# Keyboard_Buttons.net
KiCad netlist of a schematic drawn in Altium Designer
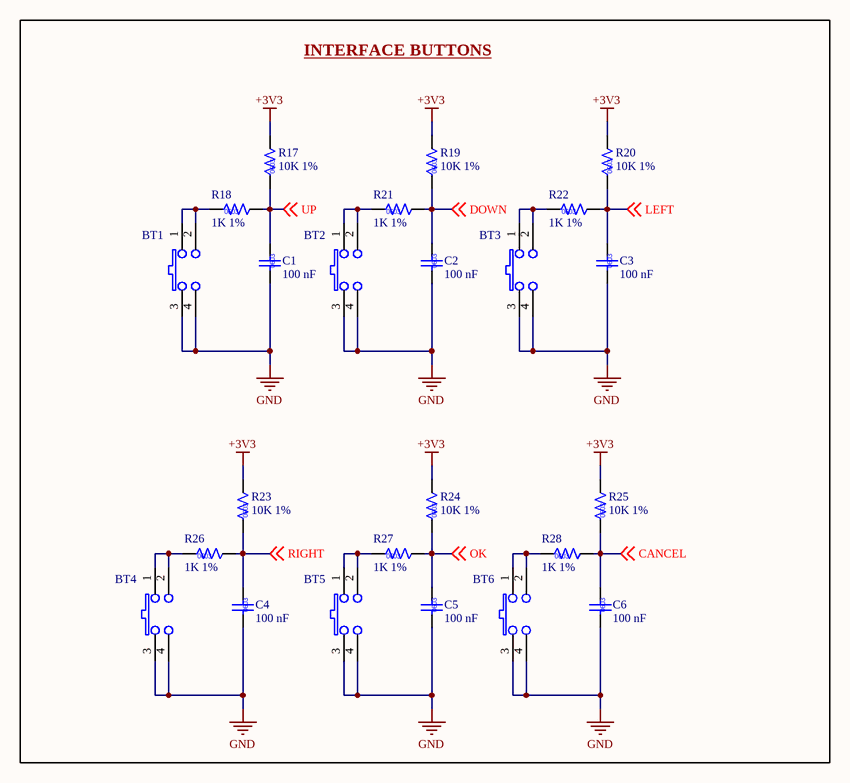
[diagram p0: Keyboard_Buttons.SchDoc]

(export (version "E")
  (design (tool "Eeschema 10.0.6"))
  (components
    (comp (ref "BT1")
      (value "TS14-1212-60-BK-260-SCR-D")
      (footprint "TS14121260BK260SCRD")
      (description "Interruptores táctiles 12 x 12 mm 6 mm 260 gf Short Crimped Black Through Hole SPST")
      (fields (field (name "MANUFACTURER") "Same Sky"))
      (libsource (lib "DDR5_Nucleo_Shield_Symbols") (part "TS14-1212-60-BK-260-SCR-D"))
    )
    (comp (ref "BT2")
      (value "TS14-1212-60-BK-260-SCR-D")
      (footprint "TS14121260BK260SCRD")
      (description "Interruptores táctiles 12 x 12 mm 6 mm 260 gf Short Crimped Black Through Hole SPST")
      (fields (field (name "MANUFACTURER") "Same Sky"))
      (libsource (lib "DDR5_Nucleo_Shield_Symbols") (part "TS14-1212-60-BK-260-SCR-D"))
    )
    (comp (ref "BT3")
      (value "TS14-1212-60-BK-260-SCR-D")
      (footprint "TS14121260BK260SCRD")
      (description "Interruptores táctiles 12 x 12 mm 6 mm 260 gf Short Crimped Black Through Hole SPST")
      (fields (field (name "MANUFACTURER") "Same Sky"))
      (libsource (lib "DDR5_Nucleo_Shield_Symbols") (part "TS14-1212-60-BK-260-SCR-D"))
    )
    (comp (ref "BT4")
      (value "TS14-1212-60-BK-260-SCR-D")
      (footprint "TS14121260BK260SCRD")
      (description "Interruptores táctiles 12 x 12 mm 6 mm 260 gf Short Crimped Black Through Hole SPST")
      (fields (field (name "MANUFACTURER") "Same Sky"))
      (libsource (lib "DDR5_Nucleo_Shield_Symbols") (part "TS14-1212-60-BK-260-SCR-D"))
    )
    (comp (ref "BT5")
      (value "TS14-1212-60-BK-260-SCR-D")
      (footprint "TS14121260BK260SCRD")
      (description "Interruptores táctiles 12 x 12 mm 6 mm 260 gf Short Crimped Black Through Hole SPST")
      (fields (field (name "MANUFACTURER") "Same Sky"))
      (libsource (lib "DDR5_Nucleo_Shield_Symbols") (part "TS14-1212-60-BK-260-SCR-D"))
    )
    (comp (ref "BT6")
      (value "TS14-1212-60-BK-260-SCR-D")
      (footprint "TS14121260BK260SCRD")
      (description "Interruptores táctiles 12 x 12 mm 6 mm 260 gf Short Crimped Black Through Hole SPST")
      (fields (field (name "MANUFACTURER") "Same Sky"))
      (libsource (lib "DDR5_Nucleo_Shield_Symbols") (part "TS14-1212-60-BK-260-SCR-D"))
    )
    (comp (ref "C1")
      (value "100 nF")
      (footprint "CC/NM 0603")
      (description "0.1 µF -20%, +80% 25V Ceramic Capacitor Y5V (F) 0603 (1608 Metric)")
      (fields
        (field (name "MANUFACTURER") "KYOCERA AVX")
        (field (name "MANUFACTURER PART NUMBER") "KGM15AV51E104ZM")
      )
      (libsource (lib "DDR5_Nucleo_Shield_Symbols") (part "KGM15AV51E104ZM"))
    )
    (comp (ref "C2")
      (value "100 nF")
      (footprint "CC/NM 0603")
      (description "0.1 µF -20%, +80% 25V Ceramic Capacitor Y5V (F) 0603 (1608 Metric)")
      (fields
        (field (name "MANUFACTURER") "KYOCERA AVX")
        (field (name "MANUFACTURER PART NUMBER") "KGM15AV51E104ZM")
      )
      (libsource (lib "DDR5_Nucleo_Shield_Symbols") (part "KGM15AV51E104ZM"))
    )
    (comp (ref "C3")
      (value "100 nF")
      (footprint "CC/NM 0603")
      (description "0.1 µF -20%, +80% 25V Ceramic Capacitor Y5V (F) 0603 (1608 Metric)")
      (fields
        (field (name "MANUFACTURER") "KYOCERA AVX")
        (field (name "MANUFACTURER PART NUMBER") "KGM15AV51E104ZM")
      )
      (libsource (lib "DDR5_Nucleo_Shield_Symbols") (part "KGM15AV51E104ZM"))
    )
    (comp (ref "C4")
      (value "100 nF")
      (footprint "CC/NM 0603")
      (description "0.1 µF -20%, +80% 25V Ceramic Capacitor Y5V (F) 0603 (1608 Metric)")
      (fields
        (field (name "MANUFACTURER") "KYOCERA AVX")
        (field (name "MANUFACTURER PART NUMBER") "KGM15AV51E104ZM")
      )
      (libsource (lib "DDR5_Nucleo_Shield_Symbols") (part "KGM15AV51E104ZM"))
    )
    (comp (ref "C5")
      (value "100 nF")
      (footprint "CC/NM 0603")
      (description "0.1 µF -20%, +80% 25V Ceramic Capacitor Y5V (F) 0603 (1608 Metric)")
      (fields
        (field (name "MANUFACTURER") "KYOCERA AVX")
        (field (name "MANUFACTURER PART NUMBER") "KGM15AV51E104ZM")
      )
      (libsource (lib "DDR5_Nucleo_Shield_Symbols") (part "KGM15AV51E104ZM"))
    )
    (comp (ref "C6")
      (value "100 nF")
      (footprint "CC/NM 0603")
      (description "0.1 µF -20%, +80% 25V Ceramic Capacitor Y5V (F) 0603 (1608 Metric)")
      (fields
        (field (name "MANUFACTURER") "KYOCERA AVX")
        (field (name "MANUFACTURER PART NUMBER") "KGM15AV51E104ZM")
      )
      (libsource (lib "DDR5_Nucleo_Shield_Symbols") (part "KGM15AV51E104ZM"))
    )
    (comp (ref "R17")
      (value "10K 1%")
      (footprint "CC/NM 0603")
      (fields
        (field (name "MANUFACTURER") "YAGEO")
        (field (name "MANUFACTURER PART NUMBER") "AC0603FR-0710KL")
      )
      (libsource (lib "DDR5_Nucleo_Shield_Symbols") (part "AC0603FR-0710KL"))
    )
    (comp (ref "R18")
      (value "1K 1%")
      (footprint "CC/NM 0603")
      (fields
        (field (name "MANUFACTURER") "YAGEO")
        (field (name "MANUFACTURER PART NUMBER") "RT0603BRD101KL")
      )
      (libsource (lib "DDR5_Nucleo_Shield_Symbols") (part "RT0603BRD101KL"))
    )
    (comp (ref "R19")
      (value "10K 1%")
      (footprint "CC/NM 0603")
      (fields
        (field (name "MANUFACTURER") "YAGEO")
        (field (name "MANUFACTURER PART NUMBER") "AC0603FR-0710KL")
      )
      (libsource (lib "DDR5_Nucleo_Shield_Symbols") (part "AC0603FR-0710KL"))
    )
    (comp (ref "R20")
      (value "10K 1%")
      (footprint "CC/NM 0603")
      (fields
        (field (name "MANUFACTURER") "YAGEO")
        (field (name "MANUFACTURER PART NUMBER") "AC0603FR-0710KL")
      )
      (libsource (lib "DDR5_Nucleo_Shield_Symbols") (part "AC0603FR-0710KL"))
    )
    (comp (ref "R21")
      (value "1K 1%")
      (footprint "CC/NM 0603")
      (fields
        (field (name "MANUFACTURER") "YAGEO")
        (field (name "MANUFACTURER PART NUMBER") "RT0603BRD101KL")
      )
      (libsource (lib "DDR5_Nucleo_Shield_Symbols") (part "RT0603BRD101KL"))
    )
    (comp (ref "R22")
      (value "1K 1%")
      (footprint "CC/NM 0603")
      (fields
        (field (name "MANUFACTURER") "YAGEO")
        (field (name "MANUFACTURER PART NUMBER") "RT0603BRD101KL")
      )
      (libsource (lib "DDR5_Nucleo_Shield_Symbols") (part "RT0603BRD101KL"))
    )
    (comp (ref "R23")
      (value "10K 1%")
      (footprint "CC/NM 0603")
      (fields
        (field (name "MANUFACTURER") "YAGEO")
        (field (name "MANUFACTURER PART NUMBER") "AC0603FR-0710KL")
      )
      (libsource (lib "DDR5_Nucleo_Shield_Symbols") (part "AC0603FR-0710KL"))
    )
    (comp (ref "R24")
      (value "10K 1%")
      (footprint "CC/NM 0603")
      (fields
        (field (name "MANUFACTURER") "YAGEO")
        (field (name "MANUFACTURER PART NUMBER") "AC0603FR-0710KL")
      )
      (libsource (lib "DDR5_Nucleo_Shield_Symbols") (part "AC0603FR-0710KL"))
    )
    (comp (ref "R25")
      (value "10K 1%")
      (footprint "CC/NM 0603")
      (fields
        (field (name "MANUFACTURER") "YAGEO")
        (field (name "MANUFACTURER PART NUMBER") "AC0603FR-0710KL")
      )
      (libsource (lib "DDR5_Nucleo_Shield_Symbols") (part "AC0603FR-0710KL"))
    )
    (comp (ref "R26")
      (value "1K 1%")
      (footprint "CC/NM 0603")
      (fields
        (field (name "MANUFACTURER") "YAGEO")
        (field (name "MANUFACTURER PART NUMBER") "RT0603BRD101KL")
      )
      (libsource (lib "DDR5_Nucleo_Shield_Symbols") (part "RT0603BRD101KL"))
    )
    (comp (ref "R27")
      (value "1K 1%")
      (footprint "CC/NM 0603")
      (fields
        (field (name "MANUFACTURER") "YAGEO")
        (field (name "MANUFACTURER PART NUMBER") "RT0603BRD101KL")
      )
      (libsource (lib "DDR5_Nucleo_Shield_Symbols") (part "RT0603BRD101KL"))
    )
    (comp (ref "R28")
      (value "1K 1%")
      (footprint "CC/NM 0603")
      (fields
        (field (name "MANUFACTURER") "YAGEO")
        (field (name "MANUFACTURER PART NUMBER") "RT0603BRD101KL")
      )
      (libsource (lib "DDR5_Nucleo_Shield_Symbols") (part "RT0603BRD101KL"))
    )
  )
  (nets
    (net (code "1") (name "+3V3") (class "Default")
      (node (ref "R17") (pin "2") (pinfunction "2_2") (pintype "passive"))
      (node (ref "R19") (pin "2") (pinfunction "2_2") (pintype "passive"))
      (node (ref "R20") (pin "2") (pinfunction "2_2") (pintype "passive"))
      (node (ref "R23") (pin "2") (pinfunction "2_2") (pintype "passive"))
      (node (ref "R24") (pin "2") (pinfunction "2_2") (pintype "passive"))
      (node (ref "R25") (pin "2") (pinfunction "2_2") (pintype "passive"))
    )
    (net (code "2") (name "CANCEL") (class "Default")
      (node (ref "C6") (pin "2") (pinfunction "2_2") (pintype "passive"))
      (node (ref "R25") (pin "1") (pinfunction "1_1") (pintype "passive"))
      (node (ref "R28") (pin "2") (pinfunction "2_2") (pintype "passive"))
    )
    (net (code "3") (name "DOWN") (class "Default")
      (node (ref "C2") (pin "2") (pinfunction "2_2") (pintype "passive"))
      (node (ref "R19") (pin "1") (pinfunction "1_1") (pintype "passive"))
      (node (ref "R21") (pin "2") (pinfunction "2_2") (pintype "passive"))
    )
    (net (code "4") (name "GND") (class "Default")
      (node (ref "BT1") (pin "3") (pinfunction "3_3") (pintype "passive"))
      (node (ref "BT1") (pin "4") (pinfunction "4_4") (pintype "passive"))
      (node (ref "BT2") (pin "3") (pinfunction "3_3") (pintype "passive"))
      (node (ref "BT2") (pin "4") (pinfunction "4_4") (pintype "passive"))
      (node (ref "BT3") (pin "3") (pinfunction "3_3") (pintype "passive"))
      (node (ref "BT3") (pin "4") (pinfunction "4_4") (pintype "passive"))
      (node (ref "BT4") (pin "3") (pinfunction "3_3") (pintype "passive"))
      (node (ref "BT4") (pin "4") (pinfunction "4_4") (pintype "passive"))
      (node (ref "BT5") (pin "3") (pinfunction "3_3") (pintype "passive"))
      (node (ref "BT5") (pin "4") (pinfunction "4_4") (pintype "passive"))
      (node (ref "BT6") (pin "3") (pinfunction "3_3") (pintype "passive"))
      (node (ref "BT6") (pin "4") (pinfunction "4_4") (pintype "passive"))
      (node (ref "C1") (pin "1") (pinfunction "1_1") (pintype "passive"))
      (node (ref "C2") (pin "1") (pinfunction "1_1") (pintype "passive"))
      (node (ref "C3") (pin "1") (pinfunction "1_1") (pintype "passive"))
      (node (ref "C4") (pin "1") (pinfunction "1_1") (pintype "passive"))
      (node (ref "C5") (pin "1") (pinfunction "1_1") (pintype "passive"))
      (node (ref "C6") (pin "1") (pinfunction "1_1") (pintype "passive"))
    )
    (net (code "5") (name "LEFT") (class "Default")
      (node (ref "C3") (pin "2") (pinfunction "2_2") (pintype "passive"))
      (node (ref "R20") (pin "1") (pinfunction "1_1") (pintype "passive"))
      (node (ref "R22") (pin "2") (pinfunction "2_2") (pintype "passive"))
    )
    (net (code "6") (name "Net-(BT1-Pad1)") (class "Default")
      (node (ref "BT1") (pin "1") (pinfunction "1_1") (pintype "passive"))
      (node (ref "BT1") (pin "2") (pinfunction "2_2") (pintype "passive"))
      (node (ref "R18") (pin "1") (pinfunction "1_1") (pintype "passive"))
    )
    (net (code "7") (name "Net-(BT2-Pad1)") (class "Default")
      (node (ref "BT2") (pin "1") (pinfunction "1_1") (pintype "passive"))
      (node (ref "BT2") (pin "2") (pinfunction "2_2") (pintype "passive"))
      (node (ref "R21") (pin "1") (pinfunction "1_1") (pintype "passive"))
    )
    (net (code "8") (name "Net-(BT3-Pad1)") (class "Default")
      (node (ref "BT3") (pin "1") (pinfunction "1_1") (pintype "passive"))
      (node (ref "BT3") (pin "2") (pinfunction "2_2") (pintype "passive"))
      (node (ref "R22") (pin "1") (pinfunction "1_1") (pintype "passive"))
    )
    (net (code "9") (name "Net-(BT4-Pad1)") (class "Default")
      (node (ref "BT4") (pin "1") (pinfunction "1_1") (pintype "passive"))
      (node (ref "BT4") (pin "2") (pinfunction "2_2") (pintype "passive"))
      (node (ref "R26") (pin "1") (pinfunction "1_1") (pintype "passive"))
    )
    (net (code "10") (name "Net-(BT5-Pad1)") (class "Default")
      (node (ref "BT5") (pin "1") (pinfunction "1_1") (pintype "passive"))
      (node (ref "BT5") (pin "2") (pinfunction "2_2") (pintype "passive"))
      (node (ref "R27") (pin "1") (pinfunction "1_1") (pintype "passive"))
    )
    (net (code "11") (name "Net-(BT6-Pad1)") (class "Default")
      (node (ref "BT6") (pin "1") (pinfunction "1_1") (pintype "passive"))
      (node (ref "BT6") (pin "2") (pinfunction "2_2") (pintype "passive"))
      (node (ref "R28") (pin "1") (pinfunction "1_1") (pintype "passive"))
    )
    (net (code "12") (name "OK") (class "Default")
      (node (ref "C5") (pin "2") (pinfunction "2_2") (pintype "passive"))
      (node (ref "R24") (pin "1") (pinfunction "1_1") (pintype "passive"))
      (node (ref "R27") (pin "2") (pinfunction "2_2") (pintype "passive"))
    )
    (net (code "13") (name "RIGHT") (class "Default")
      (node (ref "C4") (pin "2") (pinfunction "2_2") (pintype "passive"))
      (node (ref "R23") (pin "1") (pinfunction "1_1") (pintype "passive"))
      (node (ref "R26") (pin "2") (pinfunction "2_2") (pintype "passive"))
    )
    (net (code "14") (name "UP") (class "Default")
      (node (ref "C1") (pin "2") (pinfunction "2_2") (pintype "passive"))
      (node (ref "R17") (pin "1") (pinfunction "1_1") (pintype "passive"))
      (node (ref "R18") (pin "2") (pinfunction "2_2") (pintype "passive"))
    )
  )
)
